# Adafruit_T-Cobbler.net
KiCad netlist of a schematic drawn in EAGLE
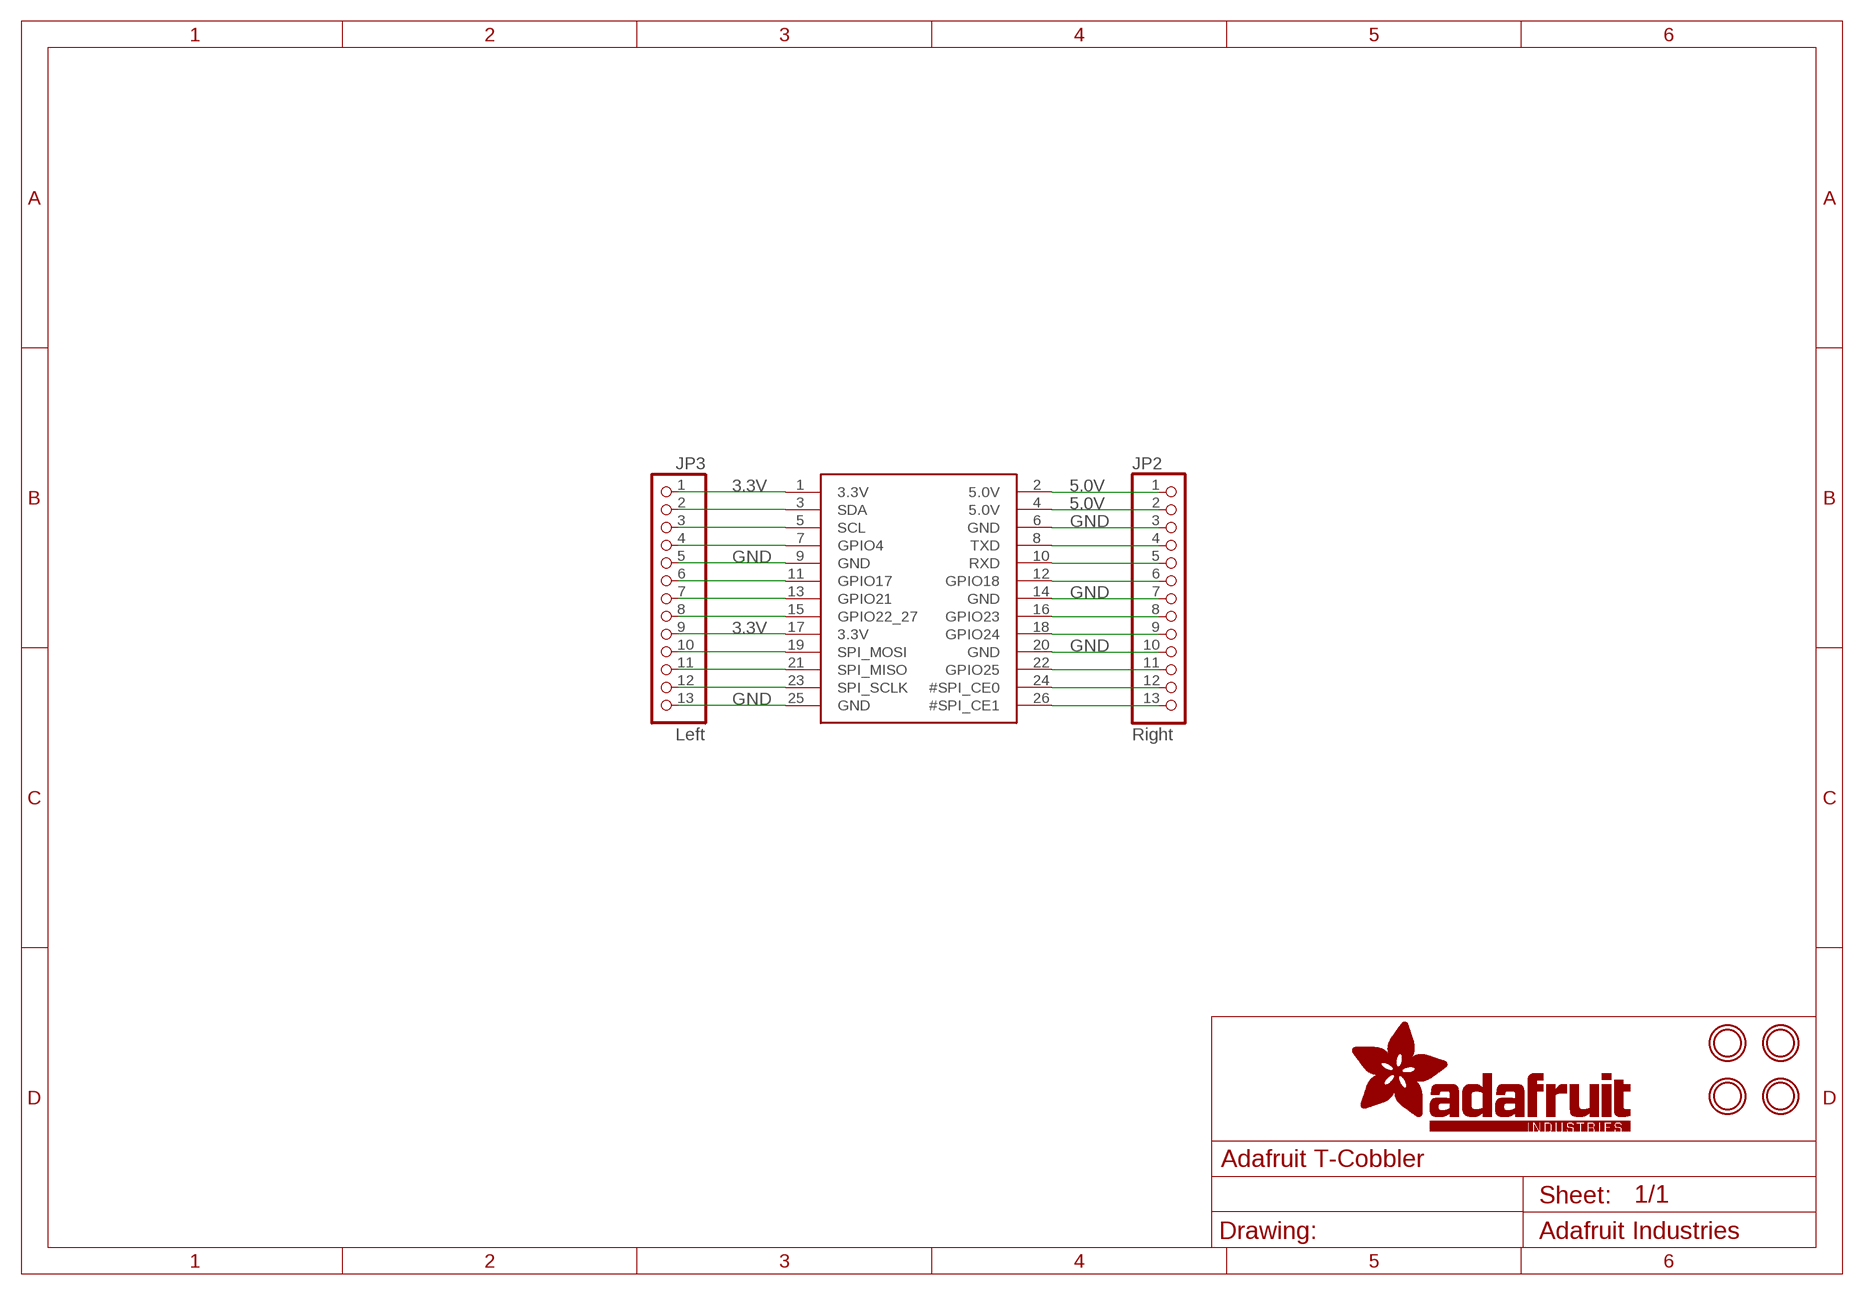
[diagram p0: schematic, sheet 1]

(export (version "E")
  (design (tool "Eeschema 10.0.6"))
  (components
    (comp (ref "JP1")
      (value "PI")
      (footprint "eagle-import:RASBERRYPI_IDC")
      (libsource (lib "eagle-import") (part "RASBERRYPI_IDC"))
    )
    (comp (ref "JP2")
      (value "Right")
      (footprint "eagle-import:1X13_ROUND_70")
      (libsource (lib "eagle-import") (part "HEADER-1X13"))
    )
    (comp (ref "JP3")
      (value "Left")
      (footprint "eagle-import:1X13_ROUND_70")
      (libsource (lib "eagle-import") (part "HEADER-1X13"))
    )
    (comp (ref "U$2")
      (value "MOUNTINGHOLE2.5")
      (footprint "eagle-import:MOUNTINGHOLE_2.5_PLATED")
      (libsource (lib "eagle-import") (part "MOUNTINGHOLE2.5"))
    )
    (comp (ref "U$3")
      (value "MOUNTINGHOLE2.5")
      (footprint "eagle-import:MOUNTINGHOLE_2.5_PLATED")
      (libsource (lib "eagle-import") (part "MOUNTINGHOLE2.5"))
    )
    (comp (ref "U$4")
      (value "MOUNTINGHOLE2.5")
      (footprint "eagle-import:MOUNTINGHOLE_2.5_PLATED")
      (libsource (lib "eagle-import") (part "MOUNTINGHOLE2.5"))
    )
    (comp (ref "U$5")
      (value "MOUNTINGHOLE2.5")
      (footprint "eagle-import:MOUNTINGHOLE_2.5_PLATED")
      (libsource (lib "eagle-import") (part "MOUNTINGHOLE2.5"))
    )
  )
  (nets
    (net (code "1") (name "/3.3V") (class "Default")
      (node (ref "JP1") (pin "1") (pinfunction "3.3V_1") (pintype "power_in"))
      (node (ref "JP1") (pin "17") (pinfunction "3.3V_17") (pintype "power_in"))
      (node (ref "JP3") (pin "1") (pinfunction "1_1") (pintype "passive"))
      (node (ref "JP3") (pin "9") (pinfunction "9_9") (pintype "passive"))
    )
    (net (code "2") (name "/5.0V") (class "Default")
      (node (ref "JP1") (pin "2") (pinfunction "5.0V_2") (pintype "power_in"))
      (node (ref "JP1") (pin "4") (pinfunction "5.0V_4") (pintype "power_in"))
      (node (ref "JP2") (pin "1") (pinfunction "1_1") (pintype "passive"))
      (node (ref "JP2") (pin "2") (pinfunction "2_2") (pintype "passive"))
    )
    (net (code "3") (name "/GND") (class "Default")
      (node (ref "JP1") (pin "14") (pinfunction "GND_14") (pintype "power_in"))
      (node (ref "JP1") (pin "20") (pinfunction "GND_20") (pintype "power_in"))
      (node (ref "JP1") (pin "25") (pinfunction "GND_25") (pintype "power_in"))
      (node (ref "JP1") (pin "6") (pinfunction "GND_6") (pintype "power_in"))
      (node (ref "JP1") (pin "9") (pinfunction "GND_9") (pintype "power_in"))
      (node (ref "JP2") (pin "10") (pinfunction "10_10") (pintype "passive"))
      (node (ref "JP2") (pin "3") (pinfunction "3_3") (pintype "passive"))
      (node (ref "JP2") (pin "7") (pinfunction "7_7") (pintype "passive"))
      (node (ref "JP3") (pin "13") (pinfunction "13_13") (pintype "passive"))
      (node (ref "JP3") (pin "5") (pinfunction "5_5") (pintype "passive"))
    )
    (net (code "4") (name "Net-(JP1-#SPI_CE0)") (class "Default")
      (node (ref "JP1") (pin "24") (pinfunction "#SPI_CE0_24") (pintype "bidirectional"))
      (node (ref "JP2") (pin "12") (pinfunction "12_12") (pintype "passive"))
    )
    (net (code "5") (name "Net-(JP1-#SPI_CE1)") (class "Default")
      (node (ref "JP1") (pin "26") (pinfunction "#SPI_CE1_26") (pintype "bidirectional"))
      (node (ref "JP2") (pin "13") (pinfunction "13_13") (pintype "passive"))
    )
    (net (code "6") (name "Net-(JP1-GPIO4)") (class "Default")
      (node (ref "JP1") (pin "7") (pinfunction "GPIO4_7") (pintype "bidirectional"))
      (node (ref "JP3") (pin "4") (pinfunction "4_4") (pintype "passive"))
    )
    (net (code "7") (name "Net-(JP1-GPIO17)") (class "Default")
      (node (ref "JP1") (pin "11") (pinfunction "GPIO17_11") (pintype "bidirectional"))
      (node (ref "JP3") (pin "6") (pinfunction "6_6") (pintype "passive"))
    )
    (net (code "8") (name "Net-(JP1-GPIO18)") (class "Default")
      (node (ref "JP1") (pin "12") (pinfunction "GPIO18_12") (pintype "bidirectional"))
      (node (ref "JP2") (pin "6") (pinfunction "6_6") (pintype "passive"))
    )
    (net (code "9") (name "Net-(JP1-GPIO21)") (class "Default")
      (node (ref "JP1") (pin "13") (pinfunction "GPIO21_13") (pintype "bidirectional"))
      (node (ref "JP3") (pin "7") (pinfunction "7_7") (pintype "passive"))
    )
    (net (code "10") (name "Net-(JP1-GPIO22_27)") (class "Default")
      (node (ref "JP1") (pin "15") (pinfunction "GPIO22_27_15") (pintype "bidirectional"))
      (node (ref "JP3") (pin "8") (pinfunction "8_8") (pintype "passive"))
    )
    (net (code "11") (name "Net-(JP1-GPIO23)") (class "Default")
      (node (ref "JP1") (pin "16") (pinfunction "GPIO23_16") (pintype "bidirectional"))
      (node (ref "JP2") (pin "8") (pinfunction "8_8") (pintype "passive"))
    )
    (net (code "12") (name "Net-(JP1-GPIO24)") (class "Default")
      (node (ref "JP1") (pin "18") (pinfunction "GPIO24_18") (pintype "bidirectional"))
      (node (ref "JP2") (pin "9") (pinfunction "9_9") (pintype "passive"))
    )
    (net (code "13") (name "Net-(JP1-GPIO25)") (class "Default")
      (node (ref "JP1") (pin "22") (pinfunction "GPIO25_22") (pintype "bidirectional"))
      (node (ref "JP2") (pin "11") (pinfunction "11_11") (pintype "passive"))
    )
    (net (code "14") (name "Net-(JP1-RXD)") (class "Default")
      (node (ref "JP1") (pin "10") (pinfunction "RXD_10") (pintype "input"))
      (node (ref "JP2") (pin "5") (pinfunction "5_5") (pintype "passive"))
    )
    (net (code "15") (name "Net-(JP1-SCL)") (class "Default")
      (node (ref "JP1") (pin "5") (pinfunction "SCL_5") (pintype "bidirectional"))
      (node (ref "JP3") (pin "3") (pinfunction "3_3") (pintype "passive"))
    )
    (net (code "16") (name "Net-(JP1-SDA)") (class "Default")
      (node (ref "JP1") (pin "3") (pinfunction "SDA_3") (pintype "bidirectional"))
      (node (ref "JP3") (pin "2") (pinfunction "2_2") (pintype "passive"))
    )
    (net (code "17") (name "Net-(JP1-SPI_MISO)") (class "Default")
      (node (ref "JP1") (pin "21") (pinfunction "SPI_MISO_21") (pintype "input"))
      (node (ref "JP3") (pin "11") (pinfunction "11_11") (pintype "passive"))
    )
    (net (code "18") (name "Net-(JP1-SPI_MOSI)") (class "Default")
      (node (ref "JP1") (pin "19") (pinfunction "SPI_MOSI_19") (pintype "bidirectional"))
      (node (ref "JP3") (pin "10") (pinfunction "10_10") (pintype "passive"))
    )
    (net (code "19") (name "Net-(JP1-SPI_SCLK)") (class "Default")
      (node (ref "JP1") (pin "23") (pinfunction "SPI_SCLK_23") (pintype "bidirectional"))
      (node (ref "JP3") (pin "12") (pinfunction "12_12") (pintype "passive"))
    )
    (net (code "20") (name "Net-(JP1-TXD)") (class "Default")
      (node (ref "JP1") (pin "8") (pinfunction "TXD_8") (pintype "output"))
      (node (ref "JP2") (pin "4") (pinfunction "4_4") (pintype "passive"))
    )
  )
)
